# main.net
KiCad netlist of a schematic drawn in Altium Designer
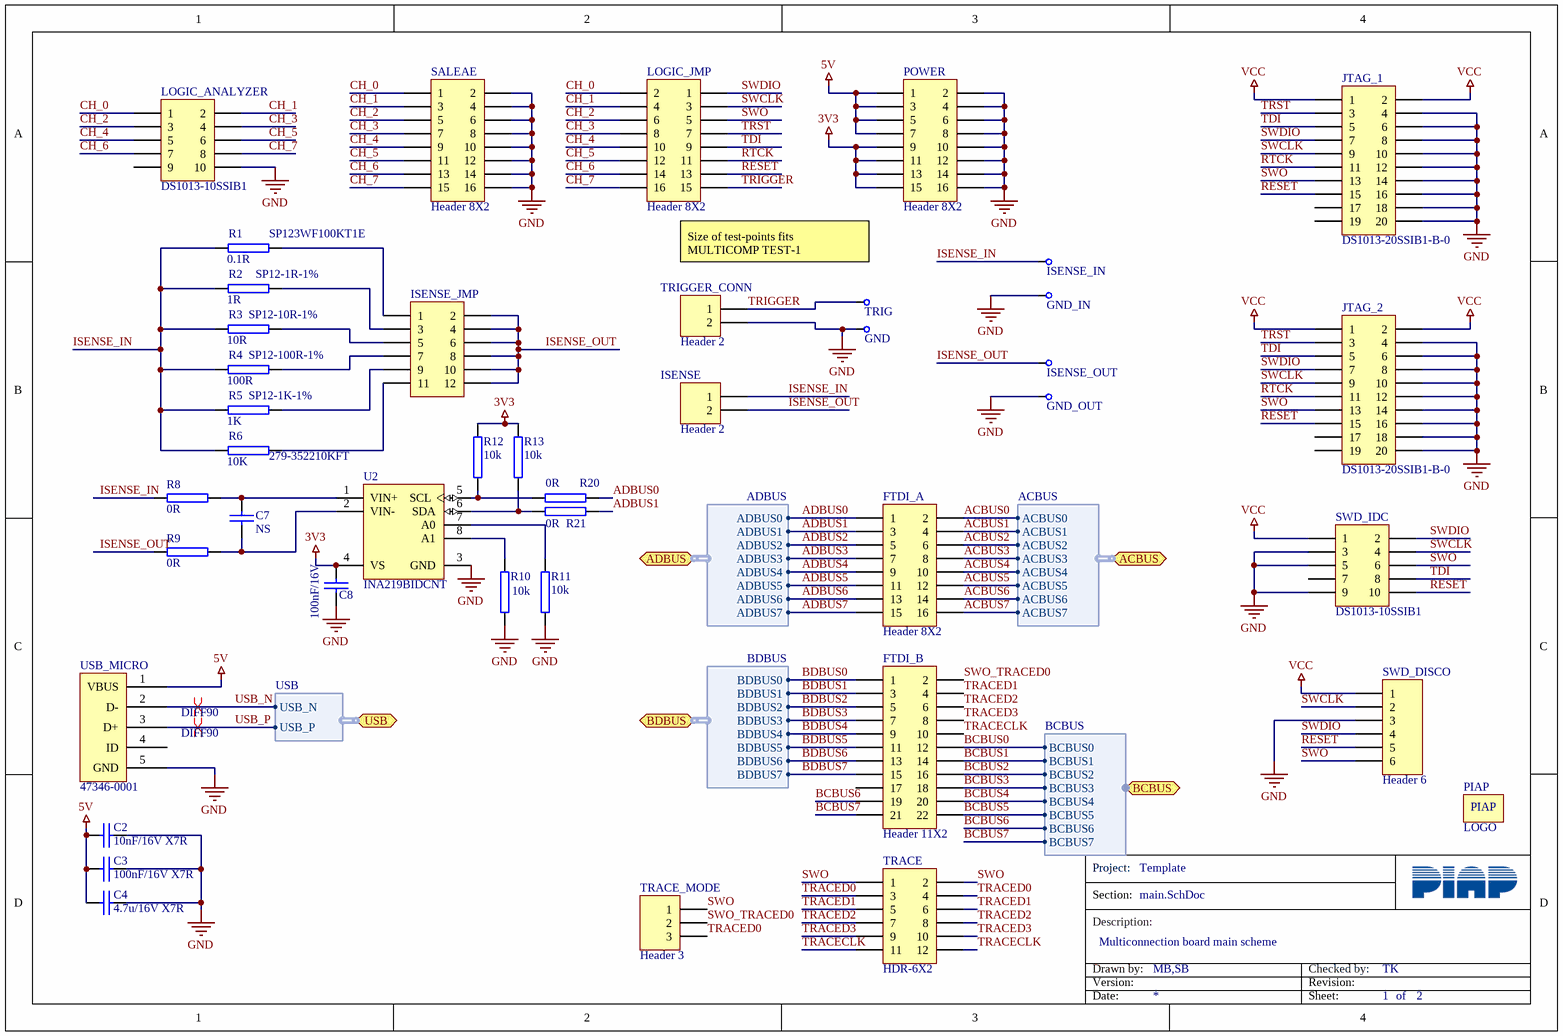
[diagram p0: main.SchDoc]

(export (version "E")
  (design (tool "Eeschema 10.0.6"))
  (components
    (comp (ref "C2")
      (value "10nF/16V X7R")
      (footprint "packages:0805")
      (description "Chip Capacitor 10nF/16V X7R")
      (fields (field (name "EMAIL") "AGrabowska@farnell.com"))
      (libsource (lib "capacitors") (part "n100"))
    )
    (comp (ref "C3")
      (value "100nF/16V X7R")
      (footprint "packages:0805")
      (description "Chip Capacitor 100nF/16V X7R")
      (fields (field (name "EMAIL") "AGrabowska@farnell.com"))
      (libsource (lib "capacitors") (part "n100"))
    )
    (comp (ref "C4")
      (value "4.7u/16V X7R")
      (footprint "packages:0805")
      (description "Chip Capacitor 4.7u/16V X7R")
      (fields (field (name "EMAIL") "AGrabowska@farnell.com"))
      (libsource (lib "capacitors") (part "n100"))
    )
    (comp (ref "C7")
      (value "NS")
      (footprint "packages:0603")
      (fields (field (name "EMAIL") "AGrabowska@farnell.com"))
      (libsource (lib "capacitors") (part "n100"))
    )
    (comp (ref "C8")
      (value "100nF/16V")
      (footprint "packages:0402")
      (description "NS")
      (fields (field (name "EMAIL") "AGrabowska@farnell.com"))
      (libsource (lib "capacitors") (part "n100"))
    )
    (comp (ref "FTDI_A")
      (value "Header 8X2")
      (footprint "connectors:HDR2X8")
      (description "Header, 16-Pin, Dual row, 2.54mm")
      (libsource (lib "") (part "Header 8X2_1"))
    )
    (comp (ref "FTDI_B")
      (value "Header 11X2")
      (footprint "connectors:HDR2X11")
      (description "Header, 22-Pin, Dual row, 2.54mm")
      (libsource (lib "connectors") (part "Header 11X2"))
    )
    (comp (ref "GND")
      (value "TEST_POINT_THT")
      (footprint "TEST_POINT_THT")
      (libsource (lib "no_bom") (part "TEST_POINT_THT"))
    )
    (comp (ref "GND_IN")
      (value "TEST_POINT_THT")
      (footprint "TEST_POINT_THT")
      (libsource (lib "no_bom") (part "TEST_POINT_THT"))
    )
    (comp (ref "GND_OUT")
      (value "TEST_POINT_THT")
      (footprint "TEST_POINT_THT")
      (libsource (lib "no_bom") (part "TEST_POINT_THT"))
    )
    (comp (ref "ISENSE")
      (value "Header 2")
      (footprint "HDR1X2")
      (description "Header, 2-Pin,  2.54mm")
      (libsource (lib "connectors") (part "Header 2"))
    )
    (comp (ref "ISENSE_IN")
      (value "TEST_POINT_THT")
      (footprint "TEST_POINT_THT")
      (libsource (lib "no_bom") (part "TEST_POINT_THT"))
    )
    (comp (ref "ISENSE_JMP")
      (value "~")
      (footprint "HDR2X6")
      (description "Header, 6-Pin, Dual row")
      (fields (field (name "PUBLISHER") "Altium Limited"))
      (libsource (lib "Miscellaneous Connectors") (part "Header 6X2"))
    )
    (comp (ref "ISENSE_OUT")
      (value "TEST_POINT_THT")
      (footprint "TEST_POINT_THT")
      (libsource (lib "no_bom") (part "TEST_POINT_THT"))
    )
    (comp (ref "JTAG_1")
      (value "DS1013-20SSIB1-B-0")
      (footprint "HDR2X10")
      (description "Header, 20-Pin, Dual row, 2.54mm")
      (libsource (lib "connectors") (part "Header 10X2"))
    )
    (comp (ref "JTAG_2")
      (value "DS1013-20SSIB1-B-0")
      (footprint "HDR2X10")
      (description "Header, 20-Pin, Dual row, 2.54mm")
      (libsource (lib "connectors") (part "Header 10X2"))
    )
    (comp (ref "LOGIC_ANALYZER")
      (value "DS1013-10SSIB1")
      (footprint "HDR2X5 socet")
      (description "Header, 10-Pin, Dual row, 2.54mm")
      (libsource (lib "connectors") (part "Header 5X2"))
    )
    (comp (ref "LOGIC_JMP")
      (value "Header 8X2")
      (footprint "HDR2X8")
      (description "Header, 16-Pin, Dual row, 2.54mm")
      (libsource (lib "connectors") (part "Header 8X2"))
    )
    (comp (ref "PIAP")
      (value "LOGO")
      (footprint "PIAP_5mm")
      (description "Logo PIAP")
      (libsource (lib "no_bom") (part "LOGO"))
    )
    (comp (ref "POWER")
      (value "Header 8X2")
      (footprint "HDR2X8")
      (description "Header, 16-Pin, Dual row, 2.54mm")
      (libsource (lib "") (part "Header 8X2_1"))
    )
    (comp (ref "R1")
      (value "0.1R")
      (footprint "packages:2512")
      (description "Resistor 0.1R 3W 1%")
      (fields
        (field (name "MANUFACTURER") "Royal Electronic Factory")
        (field (name "MANUFACTURER PART NUMBER") "SP123WF100KT1E")
      )
      (libsource (lib "resistors") (part "1R"))
    )
    (comp (ref "R2")
      (value "1R")
      (footprint "packages:2512")
      (description "Resistor 1R 3W 1%")
      (fields
        (field (name "SUPPLIER PART NUMBER 1") "SP12-1R-1%")
        (field (name "MANUFACTURER") "Royal Electronic Factory")
        (field (name "MANUFACTURER PART NUMBER") "SP123WF100KT1E")
      )
      (libsource (lib "resistors") (part "1R"))
    )
    (comp (ref "R3")
      (value "10R")
      (footprint "packages:2512")
      (description "Resistor 10R 3W 1%")
      (fields
        (field (name "SUPPLIER PART NUMBER 1") "SP12-10R-1%")
        (field (name "MANUFACTURER") "Royal Electronic Factory")
        (field (name "MANUFACTURER PART NUMBER") "SP123WF100JT1E")
      )
      (libsource (lib "resistors") (part "1R"))
    )
    (comp (ref "R4")
      (value "100R")
      (footprint "packages:2512")
      (description "Resistor 100R 2W 1%")
      (fields
        (field (name "SUPPLIER PART NUMBER 1") "SP12-100R-1%")
        (field (name "MANUFACTURER") "Royal Electronic Factory")
        (field (name "MANUFACTURER PART NUMBER") "SP123WJ0101T1E")
      )
      (libsource (lib "resistors") (part "1R"))
    )
    (comp (ref "R5")
      (value "1K")
      (footprint "packages:2512")
      (description "Resistor 1k 2W 1%")
      (fields
        (field (name "SUPPLIER PART NUMBER 1") "SP12-1K-1%")
        (field (name "MANUFACTURER") "Royal Electronic Factory")
        (field (name "MANUFACTURER PART NUMBER") "SP123WF1001T1E")
      )
      (libsource (lib "resistors") (part "1R"))
    )
    (comp (ref "R6")
      (value "10K")
      (footprint "packages:2512")
      (description "Resistor 10K 3W 1%")
      (fields
        (field (name "MANUFACTURER") "Royal Electronic Factory")
        (field (name "MANUFACTURER PART NUMBER") "SP123WF100KT1E")
        (field (name "SUPPLIER PART NUMBER 3") "279-352210KFT")
      )
      (libsource (lib "resistors") (part "1R"))
    )
    (comp (ref "R8")
      (value "0R")
      (footprint "packages:0603")
      (description "Chip Resistor 0Ohm 0.25W")
      (libsource (lib "resistors") (part "k100"))
    )
    (comp (ref "R9")
      (value "0R")
      (footprint "packages:0603")
      (description "Chip Resistor 0 Ohm 0.25W")
      (libsource (lib "resistors") (part "k100"))
    )
    (comp (ref "R10")
      (value "10k")
      (footprint "packages:0603")
      (description "Chip Resistor 0Ohm 0.25W")
      (libsource (lib "resistors") (part "k100"))
    )
    (comp (ref "R11")
      (value "10k")
      (footprint "packages:0603")
      (description "Chip Resistor 0Ohm 0.25W")
      (libsource (lib "resistors") (part "k100"))
    )
    (comp (ref "R12")
      (value "10k")
      (footprint "packages:0603")
      (description "Chip Resistor 0Ohm 0.25W")
      (libsource (lib "resistors") (part "k100"))
    )
    (comp (ref "R13")
      (value "10k")
      (footprint "packages:0603")
      (description "Chip Resistor 0Ohm 0.25W")
      (libsource (lib "resistors") (part "k100"))
    )
    (comp (ref "R20")
      (value "0R")
      (footprint "packages:0603")
      (description "Chip Resistor 0Ohm 0.25W")
      (libsource (lib "resistors") (part "k100"))
    )
    (comp (ref "R21")
      (value "0R")
      (footprint "packages:0603")
      (description "Chip Resistor 0Ohm 0.25W")
      (libsource (lib "resistors") (part "k100"))
    )
    (comp (ref "SALEAE")
      (value "Header 8X2")
      (footprint "HDR2X8")
      (description "Header, 16-Pin, Dual row, 2.54mm")
      (libsource (lib "") (part "Header 8X2_1"))
    )
    (comp (ref "SWD_DISCO")
      (value "Header 6")
      (footprint "connectors:HDR1X6")
      (description "Header, 6-Pin, 2.54mm")
      (libsource (lib "connectors") (part "Header 6"))
    )
    (comp (ref "SWD_IDC")
      (value "DS1013-10SSIB1")
      (footprint "HDR2X5 socet")
      (description "Header, 10-Pin, Dual row, 2.54mm")
      (libsource (lib "connectors") (part "Header 5X2"))
    )
    (comp (ref "TRACE")
      (value "HDR-6X2")
      (footprint "connectors:HDR2X6")
      (description "Header, 12-Pin, Dual row, SMD, 2.54mm")
      (libsource (lib "connectors") (part "Header 6X2"))
    )
    (comp (ref "TRACE_MODE")
      (value "Header 3")
      (footprint "connectors:HDR1X3")
      (description "Header, 3-Pin,  2.54mm")
      (libsource (lib "connectors") (part "Header 3"))
    )
    (comp (ref "TRIG")
      (value "TEST_POINT_THT")
      (footprint "TEST_POINT_THT")
      (libsource (lib "no_bom") (part "TEST_POINT_THT"))
    )
    (comp (ref "TRIGGER_CONN")
      (value "Header 2")
      (footprint "HDR1X2")
      (description "Header, 2-Pin,  2.54mm")
      (libsource (lib "connectors") (part "Header 2"))
    )
    (comp (ref "U2")
      (value "INA219BIDCNT")
      (footprint "DCN0008A_M")
      (fields (field (name "MANUFACTURER") "Texas Instruments"))
      (libsource (lib "Altium Content Vault") (part "TI-INA219DCN8"))
    )
    (comp (ref "USB_MICRO")
      (value "47346-0001")
      (footprint "47346-0001")
      (libsource (lib "connectors") (part "47346-0001"))
    )
  )
  (nets
    (net (code "6") (name "/ACBUS0") (class "Default")
      (node (ref "FTDI_A") (pin "2") (pinfunction "2_2") (pintype "passive"))
    )
    (net (code "7") (name "/ACBUS1") (class "Default")
      (node (ref "FTDI_A") (pin "4") (pinfunction "4_4") (pintype "passive"))
    )
    (net (code "8") (name "/ACBUS2") (class "Default")
      (node (ref "FTDI_A") (pin "6") (pinfunction "6_6") (pintype "passive"))
    )
    (net (code "9") (name "/ACBUS3") (class "Default")
      (node (ref "FTDI_A") (pin "8") (pinfunction "8_8") (pintype "passive"))
    )
    (net (code "10") (name "/ACBUS4") (class "Default")
      (node (ref "FTDI_A") (pin "10") (pinfunction "10_10") (pintype "passive"))
    )
    (net (code "11") (name "/ACBUS5") (class "Default")
      (node (ref "FTDI_A") (pin "12") (pinfunction "12_12") (pintype "passive"))
    )
    (net (code "12") (name "/ACBUS6") (class "Default")
      (node (ref "FTDI_A") (pin "14") (pinfunction "14_14") (pintype "passive"))
    )
    (net (code "13") (name "/ACBUS7") (class "Default")
      (node (ref "FTDI_A") (pin "16") (pinfunction "16_16") (pintype "passive"))
    )
    (net (code "14") (name "/ADBUS0") (class "Default")
      (node (ref "FTDI_A") (pin "1") (pinfunction "1_1") (pintype "passive"))
      (node (ref "R20") (pin "1") (pinfunction "1_1") (pintype "passive"))
    )
    (net (code "15") (name "/ADBUS1") (class "Default")
      (node (ref "FTDI_A") (pin "3") (pinfunction "3_3") (pintype "passive"))
      (node (ref "R21") (pin "1") (pinfunction "1_1") (pintype "passive"))
    )
    (net (code "16") (name "/ADBUS2") (class "Default")
      (node (ref "FTDI_A") (pin "5") (pinfunction "5_5") (pintype "passive"))
    )
    (net (code "17") (name "/ADBUS3") (class "Default")
      (node (ref "FTDI_A") (pin "7") (pinfunction "7_7") (pintype "passive"))
    )
    (net (code "18") (name "/ADBUS4") (class "Default")
      (node (ref "FTDI_A") (pin "9") (pinfunction "9_9") (pintype "passive"))
    )
    (net (code "19") (name "/ADBUS5") (class "Default")
      (node (ref "FTDI_A") (pin "11") (pinfunction "11_11") (pintype "passive"))
    )
    (net (code "20") (name "/ADBUS6") (class "Default")
      (node (ref "FTDI_A") (pin "13") (pinfunction "13_13") (pintype "passive"))
    )
    (net (code "21") (name "/ADBUS7") (class "Default")
      (node (ref "FTDI_A") (pin "15") (pinfunction "15_15") (pintype "passive"))
    )
    (net (code "22") (name "/BCBUS0") (class "Default")
      (node (ref "FTDI_B") (pin "12") (pinfunction "12_12") (pintype "passive"))
    )
    (net (code "23") (name "/BCBUS1") (class "Default")
      (node (ref "FTDI_B") (pin "14") (pinfunction "14_14") (pintype "passive"))
    )
    (net (code "24") (name "/BCBUS2") (class "Default")
      (node (ref "FTDI_B") (pin "16") (pinfunction "16_16") (pintype "passive"))
    )
    (net (code "25") (name "/BCBUS3") (class "Default")
      (node (ref "FTDI_B") (pin "18") (pinfunction "18_18") (pintype "passive"))
    )
    (net (code "26") (name "/BCBUS4") (class "Default")
      (node (ref "FTDI_B") (pin "20") (pinfunction "20_20") (pintype "passive"))
    )
    (net (code "27") (name "/BCBUS5") (class "Default")
      (node (ref "FTDI_B") (pin "22") (pinfunction "22_22") (pintype "passive"))
    )
    (net (code "28") (name "/BCBUS6") (class "Default")
      (node (ref "FTDI_B") (pin "19") (pinfunction "19_19") (pintype "passive"))
    )
    (net (code "29") (name "/BCBUS7") (class "Default")
      (node (ref "FTDI_B") (pin "21") (pinfunction "21_21") (pintype "passive"))
    )
    (net (code "30") (name "/BDBUS0") (class "Default")
      (node (ref "FTDI_B") (pin "1") (pinfunction "1_1") (pintype "passive"))
    )
    (net (code "31") (name "/BDBUS1") (class "Default")
      (node (ref "FTDI_B") (pin "3") (pinfunction "3_3") (pintype "passive"))
    )
    (net (code "32") (name "/BDBUS2") (class "Default")
      (node (ref "FTDI_B") (pin "5") (pinfunction "5_5") (pintype "passive"))
    )
    (net (code "33") (name "/BDBUS3") (class "Default")
      (node (ref "FTDI_B") (pin "7") (pinfunction "7_7") (pintype "passive"))
    )
    (net (code "34") (name "/BDBUS4") (class "Default")
      (node (ref "FTDI_B") (pin "9") (pinfunction "9_9") (pintype "passive"))
    )
    (net (code "35") (name "/BDBUS5") (class "Default")
      (node (ref "FTDI_B") (pin "11") (pinfunction "11_11") (pintype "passive"))
    )
    (net (code "36") (name "/BDBUS6") (class "Default")
      (node (ref "FTDI_B") (pin "13") (pinfunction "13_13") (pintype "passive"))
    )
    (net (code "37") (name "/BDBUS7") (class "Default")
      (node (ref "FTDI_B") (pin "15") (pinfunction "15_15") (pintype "passive"))
    )
    (net (code "38") (name "/CH_0") (class "Default")
      (node (ref "LOGIC_ANALYZER") (pin "1") (pinfunction "1_1") (pintype "passive"))
      (node (ref "LOGIC_JMP") (pin "2") (pinfunction "2_2") (pintype "passive"))
      (node (ref "SALEAE") (pin "1") (pinfunction "1_1") (pintype "passive"))
    )
    (net (code "39") (name "/CH_1") (class "Default")
      (node (ref "LOGIC_ANALYZER") (pin "2") (pinfunction "2_2") (pintype "passive"))
      (node (ref "LOGIC_JMP") (pin "4") (pinfunction "4_4") (pintype "passive"))
      (node (ref "SALEAE") (pin "3") (pinfunction "3_3") (pintype "passive"))
    )
    (net (code "40") (name "/CH_2") (class "Default")
      (node (ref "LOGIC_ANALYZER") (pin "3") (pinfunction "3_3") (pintype "passive"))
      (node (ref "LOGIC_JMP") (pin "6") (pinfunction "6_6") (pintype "passive"))
      (node (ref "SALEAE") (pin "5") (pinfunction "5_5") (pintype "passive"))
    )
    (net (code "41") (name "/CH_3") (class "Default")
      (node (ref "LOGIC_ANALYZER") (pin "4") (pinfunction "4_4") (pintype "passive"))
      (node (ref "LOGIC_JMP") (pin "8") (pinfunction "8_8") (pintype "passive"))
      (node (ref "SALEAE") (pin "7") (pinfunction "7_7") (pintype "passive"))
    )
    (net (code "42") (name "/CH_4") (class "Default")
      (node (ref "LOGIC_ANALYZER") (pin "5") (pinfunction "5_5") (pintype "passive"))
      (node (ref "LOGIC_JMP") (pin "10") (pinfunction "10_10") (pintype "passive"))
      (node (ref "SALEAE") (pin "9") (pinfunction "9_9") (pintype "passive"))
    )
    (net (code "43") (name "/CH_5") (class "Default")
      (node (ref "LOGIC_ANALYZER") (pin "6") (pinfunction "6_6") (pintype "passive"))
      (node (ref "LOGIC_JMP") (pin "12") (pinfunction "12_12") (pintype "passive"))
      (node (ref "SALEAE") (pin "11") (pinfunction "11_11") (pintype "passive"))
    )
    (net (code "44") (name "/CH_6") (class "Default")
      (node (ref "LOGIC_ANALYZER") (pin "7") (pinfunction "7_7") (pintype "passive"))
      (node (ref "LOGIC_JMP") (pin "14") (pinfunction "14_14") (pintype "passive"))
      (node (ref "SALEAE") (pin "13") (pinfunction "13_13") (pintype "passive"))
    )
    (net (code "45") (name "/CH_7") (class "Default")
      (node (ref "LOGIC_ANALYZER") (pin "8") (pinfunction "8_8") (pintype "passive"))
      (node (ref "LOGIC_JMP") (pin "16") (pinfunction "16_16") (pintype "passive"))
      (node (ref "SALEAE") (pin "15") (pinfunction "15_15") (pintype "passive"))
    )
    (net (code "46") (name "/ISENSE_IN") (class "Default")
      (node (ref "ISENSE") (pin "1") (pinfunction "1_1") (pintype "passive"))
      (node (ref "ISENSE_IN") (pin "1") (pinfunction "1_1") (pintype "passive"))
      (node (ref "R1") (pin "1") (pinfunction "1_1") (pintype "passive"))
      (node (ref "R2") (pin "1") (pinfunction "1_1") (pintype "passive"))
      (node (ref "R3") (pin "1") (pinfunction "1_1") (pintype "passive"))
      (node (ref "R4") (pin "1") (pinfunction "1_1") (pintype "passive"))
      (node (ref "R5") (pin "1") (pinfunction "1_1") (pintype "passive"))
      (node (ref "R6") (pin "1") (pinfunction "1_1") (pintype "passive"))
      (node (ref "R8") (pin "2") (pinfunction "2_2") (pintype "passive"))
    )
    (net (code "47") (name "/ISENSE_OUT") (class "Default")
      (node (ref "ISENSE") (pin "2") (pinfunction "2_2") (pintype "passive"))
      (node (ref "ISENSE_JMP") (pin "10") (pinfunction "10_10") (pintype "passive"))
      (node (ref "ISENSE_JMP") (pin "12") (pinfunction "12_12") (pintype "passive"))
      (node (ref "ISENSE_JMP") (pin "2") (pinfunction "2_2") (pintype "passive"))
      (node (ref "ISENSE_JMP") (pin "4") (pinfunction "4_4") (pintype "passive"))
      (node (ref "ISENSE_JMP") (pin "6") (pinfunction "6_6") (pintype "passive"))
      (node (ref "ISENSE_JMP") (pin "8") (pinfunction "8_8") (pintype "passive"))
      (node (ref "ISENSE_OUT") (pin "1") (pinfunction "1_1") (pintype "passive"))
      (node (ref "R9") (pin "2") (pinfunction "2_2") (pintype "passive"))
    )
    (net (code "48") (name "/RESET") (class "Default")
      (node (ref "JTAG_1") (pin "15") (pinfunction "15_15") (pintype "passive"))
      (node (ref "JTAG_2") (pin "15") (pinfunction "15_15") (pintype "passive"))
      (node (ref "LOGIC_JMP") (pin "13") (pinfunction "13_13") (pintype "passive"))
      (node (ref "SWD_DISCO") (pin "5") (pinfunction "5_5") (pintype "passive"))
      (node (ref "SWD_IDC") (pin "10") (pinfunction "10_10") (pintype "passive"))
    )
    (net (code "49") (name "/RTCK") (class "Default")
      (node (ref "JTAG_1") (pin "11") (pinfunction "11_11") (pintype "passive"))
      (node (ref "JTAG_2") (pin "11") (pinfunction "11_11") (pintype "passive"))
      (node (ref "LOGIC_JMP") (pin "11") (pinfunction "11_11") (pintype "passive"))
    )
    (net (code "50") (name "/SWCLK") (class "Default")
      (node (ref "JTAG_1") (pin "9") (pinfunction "9_9") (pintype "passive"))
      (node (ref "JTAG_2") (pin "9") (pinfunction "9_9") (pintype "passive"))
      (node (ref "LOGIC_JMP") (pin "3") (pinfunction "3_3") (pintype "passive"))
      (node (ref "SWD_DISCO") (pin "2") (pinfunction "2_2") (pintype "passive"))
      (node (ref "SWD_IDC") (pin "4") (pinfunction "4_4") (pintype "passive"))
    )
    (net (code "51") (name "/SWDIO") (class "Default")
      (node (ref "JTAG_1") (pin "7") (pinfunction "7_7") (pintype "passive"))
      (node (ref "JTAG_2") (pin "7") (pinfunction "7_7") (pintype "passive"))
      (node (ref "LOGIC_JMP") (pin "1") (pinfunction "1_1") (pintype "passive"))
      (node (ref "SWD_DISCO") (pin "4") (pinfunction "4_4") (pintype "passive"))
      (node (ref "SWD_IDC") (pin "2") (pinfunction "2_2") (pintype "passive"))
    )
    (net (code "52") (name "/SWO") (class "Default")
      (node (ref "JTAG_1") (pin "13") (pinfunction "13_13") (pintype "passive"))
      (node (ref "JTAG_2") (pin "13") (pinfunction "13_13") (pintype "passive"))
      (node (ref "LOGIC_JMP") (pin "5") (pinfunction "5_5") (pintype "passive"))
      (node (ref "SWD_DISCO") (pin "6") (pinfunction "6_6") (pintype "passive"))
      (node (ref "SWD_IDC") (pin "6") (pinfunction "6_6") (pintype "passive"))
      (node (ref "TRACE") (pin "1") (pinfunction "1_1") (pintype "passive"))
      (node (ref "TRACE") (pin "2") (pinfunction "2_2") (pintype "passive"))
      (node (ref "TRACE_MODE") (pin "1") (pinfunction "1_1") (pintype "passive"))
    )
    (net (code "53") (name "/SWO_TRACED0") (class "Default")
      (node (ref "FTDI_B") (pin "2") (pinfunction "2_2") (pintype "passive"))
      (node (ref "TRACE_MODE") (pin "2") (pinfunction "2_2") (pintype "passive"))
    )
    (net (code "54") (name "/TDI") (class "Default")
      (node (ref "JTAG_1") (pin "5") (pinfunction "5_5") (pintype "passive"))
      (node (ref "JTAG_2") (pin "5") (pinfunction "5_5") (pintype "passive"))
      (node (ref "LOGIC_JMP") (pin "9") (pinfunction "9_9") (pintype "passive"))
      (node (ref "SWD_IDC") (pin "8") (pinfunction "8_8") (pintype "passive"))
    )
    (net (code "55") (name "/TRACECLK") (class "Default")
      (node (ref "FTDI_B") (pin "10") (pinfunction "10_10") (pintype "passive"))
      (node (ref "TRACE") (pin "11") (pinfunction "11_11") (pintype "passive"))
      (node (ref "TRACE") (pin "12") (pinfunction "12_12") (pintype "passive"))
    )
    (net (code "56") (name "/TRACED0") (class "Default")
      (node (ref "TRACE") (pin "3") (pinfunction "3_3") (pintype "passive"))
      (node (ref "TRACE") (pin "4") (pinfunction "4_4") (pintype "passive"))
      (node (ref "TRACE_MODE") (pin "3") (pinfunction "3_3") (pintype "passive"))
    )
    (net (code "57") (name "/TRACED1") (class "Default")
      (node (ref "FTDI_B") (pin "4") (pinfunction "4_4") (pintype "passive"))
      (node (ref "TRACE") (pin "5") (pinfunction "5_5") (pintype "passive"))
      (node (ref "TRACE") (pin "6") (pinfunction "6_6") (pintype "passive"))
    )
    (net (code "58") (name "/TRACED2") (class "Default")
      (node (ref "FTDI_B") (pin "6") (pinfunction "6_6") (pintype "passive"))
      (node (ref "TRACE") (pin "7") (pinfunction "7_7") (pintype "passive"))
      (node (ref "TRACE") (pin "8") (pinfunction "8_8") (pintype "passive"))
    )
    (net (code "59") (name "/TRACED3") (class "Default")
      (node (ref "FTDI_B") (pin "8") (pinfunction "8_8") (pintype "passive"))
      (node (ref "TRACE") (pin "10") (pinfunction "10_10") (pintype "passive"))
      (node (ref "TRACE") (pin "9") (pinfunction "9_9") (pintype "passive"))
    )
    (net (code "60") (name "/TRIGGER") (class "Default")
      (node (ref "LOGIC_JMP") (pin "15") (pinfunction "15_15") (pintype "passive"))
      (node (ref "TRIG") (pin "1") (pinfunction "1_1") (pintype "passive"))
      (node (ref "TRIGGER_CONN") (pin "1") (pinfunction "1_1") (pintype "passive"))
    )
    (net (code "61") (name "/TRST") (class "Default")
      (node (ref "JTAG_1") (pin "3") (pinfunction "3_3") (pintype "passive"))
      (node (ref "JTAG_2") (pin "3") (pinfunction "3_3") (pintype "passive"))
      (node (ref "LOGIC_JMP") (pin "7") (pinfunction "7_7") (pintype "passive"))
    )
    (net (code "62") (name "/USB_N") (class "Default")
      (node (ref "USB_MICRO") (pin "2") (pinfunction "D-_2") (pintype "passive"))
    )
    (net (code "63") (name "/USB_P") (class "Default")
      (node (ref "USB_MICRO") (pin "3") (pinfunction "D+_3") (pintype "passive"))
    )
    (net (code "69") (name "3V3") (class "Default")
      (node (ref "C8") (pin "1") (pinfunction "1_1") (pintype "passive"))
      (node (ref "POWER") (pin "11") (pinfunction "11_11") (pintype "passive"))
      (node (ref "POWER") (pin "13") (pinfunction "13_13") (pintype "passive"))
      (node (ref "POWER") (pin "15") (pinfunction "15_15") (pintype "passive"))
      (node (ref "POWER") (pin "9") (pinfunction "9_9") (pintype "passive"))
      (node (ref "R12") (pin "2") (pinfunction "2_2") (pintype "passive"))
      (node (ref "R13") (pin "2") (pinfunction "2_2") (pintype "passive"))
      (node (ref "U2") (pin "4") (pinfunction "VS_4") (pintype "power_in"))
    )
    (net (code "70") (name "5V") (class "Default")
      (node (ref "C2") (pin "2") (pinfunction "2_2") (pintype "passive"))
      (node (ref "C3") (pin "1") (pinfunction "1_1") (pintype "passive"))
      (node (ref "C4") (pin "2") (pinfunction "2_2") (pintype "passive"))
      (node (ref "POWER") (pin "1") (pinfunction "1_1") (pintype "passive"))
      (node (ref "POWER") (pin "3") (pinfunction "3_3") (pintype "passive"))
      (node (ref "POWER") (pin "5") (pinfunction "5_5") (pintype "passive"))
      (node (ref "POWER") (pin "7") (pinfunction "7_7") (pintype "passive"))
      (node (ref "USB_MICRO") (pin "1") (pinfunction "VBUS_1") (pintype "passive"))
    )
    (net (code "71") (name "GND") (class "Default")
      (node (ref "C2") (pin "1") (pinfunction "1_1") (pintype "passive"))
      (node (ref "C3") (pin "2") (pinfunction "2_2") (pintype "passive"))
      (node (ref "C4") (pin "1") (pinfunction "1_1") (pintype "passive"))
      (node (ref "C8") (pin "2") (pinfunction "2_2") (pintype "passive"))
      (node (ref "GND") (pin "1") (pinfunction "1_1") (pintype "passive"))
      (node (ref "GND_IN") (pin "1") (pinfunction "1_1") (pintype "passive"))
      (node (ref "GND_OUT") (pin "1") (pinfunction "1_1") (pintype "passive"))
      (node (ref "JTAG_1") (pin "10") (pinfunction "10_10") (pintype "passive"))
      (node (ref "JTAG_1") (pin "12") (pinfunction "12_12") (pintype "passive"))
      (node (ref "JTAG_1") (pin "14") (pinfunction "14_14") (pintype "passive"))
      (node (ref "JTAG_1") (pin "16") (pinfunction "16_16") (pintype "passive"))
      (node (ref "JTAG_1") (pin "18") (pinfunction "18_18") (pintype "passive"))
      (node (ref "JTAG_1") (pin "20") (pinfunction "20_20") (pintype "passive"))
      (node (ref "JTAG_1") (pin "4") (pinfunction "4_4") (pintype "passive"))
      (node (ref "JTAG_1") (pin "6") (pinfunction "6_6") (pintype "passive"))
      (node (ref "JTAG_1") (pin "8") (pinfunction "8_8") (pintype "passive"))
      (node (ref "JTAG_2") (pin "10") (pinfunction "10_10") (pintype "passive"))
      (node (ref "JTAG_2") (pin "12") (pinfunction "12_12") (pintype "passive"))
      (node (ref "JTAG_2") (pin "14") (pinfunction "14_14") (pintype "passive"))
      (node (ref "JTAG_2") (pin "16") (pinfunction "16_16") (pintype "passive"))
      (node (ref "JTAG_2") (pin "18") (pinfunction "18_18") (pintype "passive"))
      (node (ref "JTAG_2") (pin "20") (pinfunction "20_20") (pintype "passive"))
      (node (ref "JTAG_2") (pin "4") (pinfunction "4_4") (pintype "passive"))
      (node (ref "JTAG_2") (pin "6") (pinfunction "6_6") (pintype "passive"))
      (node (ref "JTAG_2") (pin "8") (pinfunction "8_8") (pintype "passive"))
      (node (ref "LOGIC_ANALYZER") (pin "10") (pinfunction "10_10") (pintype "passive"))
      (node (ref "POWER") (pin "10") (pinfunction "10_10") (pintype "passive"))
      (node (ref "POWER") (pin "12") (pinfunction "12_12") (pintype "passive"))
      (node (ref "POWER") (pin "14") (pinfunction "14_14") (pintype "passive"))
      (node (ref "POWER") (pin "16") (pinfunction "16_16") (pintype "passive"))
      (node (ref "POWER") (pin "2") (pinfunction "2_2") (pintype "passive"))
      (node (ref "POWER") (pin "4") (pinfunction "4_4") (pintype "passive"))
      (node (ref "POWER") (pin "6") (pinfunction "6_6") (pintype "passive"))
      (node (ref "POWER") (pin "8") (pinfunction "8_8") (pintype "passive"))
      (node (ref "R10") (pin "2") (pinfunction "2_2") (pintype "passive"))
      (node (ref "R11") (pin "2") (pinfunction "2_2") (pintype "passive"))
      (node (ref "SALEAE") (pin "10") (pinfunction "10_10") (pintype "passive"))
      (node (ref "SALEAE") (pin "12") (pinfunction "12_12") (pintype "passive"))
      (node (ref "SALEAE") (pin "14") (pinfunction "14_14") (pintype "passive"))
      (node (ref "SALEAE") (pin "16") (pinfunction "16_16") (pintype "passive"))
      (node (ref "SALEAE") (pin "2") (pinfunction "2_2") (pintype "passive"))
      (node (ref "SALEAE") (pin "4") (pinfunction "4_4") (pintype "passive"))
      (node (ref "SALEAE") (pin "6") (pinfunction "6_6") (pintype "passive"))
      (node (ref "SALEAE") (pin "8") (pinfunction "8_8") (pintype "passive"))
      (node (ref "SWD_DISCO") (pin "3") (pinfunction "3_3") (pintype "passive"))
      (node (ref "SWD_IDC") (pin "3") (pinfunction "3_3") (pintype "passive"))
      (node (ref "SWD_IDC") (pin "5") (pinfunction "5_5") (pintype "passive"))
      (node (ref "SWD_IDC") (pin "9") (pinfunction "9_9") (pintype "passive"))
      (node (ref "TRIGGER_CONN") (pin "2") (pinfunction "2_2") (pintype "passive"))
      (node (ref "U2") (pin "3") (pinfunction "GND_3") (pintype "power_in"))
      (node (ref "USB_MICRO") (pin "5") (pinfunction "GND_5") (pintype "passive"))
    )
    (net (code "72") (name "Net-(ISENSE_JMP-Pad1)") (class "Default")
      (node (ref "ISENSE_JMP") (pin "1") (pinfunction "1_1") (pintype "passive"))
      (node (ref "R1") (pin "2") (pinfunction "2_2") (pintype "passive"))
    )
    (net (code "73") (name "Net-(ISENSE_JMP-Pad3)") (class "Default")
      (node (ref "ISENSE_JMP") (pin "3") (pinfunction "3_3") (pintype "passive"))
      (node (ref "R2") (pin "2") (pinfunction "2_2") (pintype "passive"))
    )
    (net (code "74") (name "Net-(ISENSE_JMP-Pad5)") (class "Default")
      (node (ref "ISENSE_JMP") (pin "5") (pinfunction "5_5") (pintype "passive"))
      (node (ref "R3") (pin "2") (pinfunction "2_2") (pintype "passive"))
    )
    (net (code "75") (name "Net-(ISENSE_JMP-Pad7)") (class "Default")
      (node (ref "ISENSE_JMP") (pin "7") (pinfunction "7_7") (pintype "passive"))
      (node (ref "R4") (pin "2") (pinfunction "2_2") (pintype "passive"))
    )
    (net (code "76") (name "Net-(ISENSE_JMP-Pad9)") (class "Default")
      (node (ref "ISENSE_JMP") (pin "9") (pinfunction "9_9") (pintype "passive"))
      (node (ref "R5") (pin "2") (pinfunction "2_2") (pintype "passive"))
    )
    (net (code "77") (name "Net-(ISENSE_JMP-Pad11)") (class "Default")
      (node (ref "ISENSE_JMP") (pin "11") (pinfunction "11_11") (pintype "passive"))
      (node (ref "R6") (pin "2") (pinfunction "2_2") (pintype "passive"))
    )
    (net (code "78") (name "Net-(U2-A0)") (class "Default")
      (node (ref "R11") (pin "1") (pinfunction "1_1") (pintype "passive"))
      (node (ref "U2") (pin "7") (pinfunction "A0_7") (pintype "open_collector"))
    )
    (net (code "79") (name "Net-(U2-A1)") (class "Default")
      (node (ref "R10") (pin "1") (pinfunction "1_1") (pintype "passive"))
      (node (ref "U2") (pin "8") (pinfunction "A1_8") (pintype "open_collector"))
    )
    (net (code "80") (name "Net-(U2-SCL)") (class "Default")
      (node (ref "R12") (pin "1") (pinfunction "1_1") (pintype "passive"))
      (node (ref "R20") (pin "2") (pinfunction "2_2") (pintype "passive"))
      (node (ref "U2") (pin "5") (pinfunction "SCL_5") (pintype "bidirectional"))
    )
    (net (code "81") (name "Net-(U2-SDA)") (class "Default")
      (node (ref "R13") (pin "1") (pinfunction "1_1") (pintype "passive"))
      (node (ref "R21") (pin "2") (pinfunction "2_2") (pintype "passive"))
      (node (ref "U2") (pin "6") (pinfunction "SDA_6") (pintype "bidirectional"))
    )
    (net (code "82") (name "Net-(U2-VIN+)") (class "Default")
      (node (ref "C7") (pin "2") (pinfunction "2_2") (pintype "passive"))
      (node (ref "R8") (pin "1") (pinfunction "1_1") (pintype "passive"))
      (node (ref "U2") (pin "1") (pinfunction "VIN+_1") (pintype "open_collector"))
    )
    (net (code "83") (name "Net-(U2-VIN-)") (class "Default")
      (node (ref "C7") (pin "1") (pinfunction "1_1") (pintype "passive"))
      (node (ref "R9") (pin "1") (pinfunction "1_1") (pintype "passive"))
      (node (ref "U2") (pin "2") (pinfunction "VIN-_2") (pintype "open_collector"))
    )
    (net (code "84") (name "VCC") (class "Default")
      (node (ref "JTAG_1") (pin "1") (pinfunction "1_1") (pintype "passive"))
      (node (ref "JTAG_1") (pin "2") (pinfunction "2_2") (pintype "passive"))
      (node (ref "JTAG_2") (pin "1") (pinfunction "1_1") (pintype "passive"))
      (node (ref "JTAG_2") (pin "2") (pinfunction "2_2") (pintype "passive"))
      (node (ref "SWD_DISCO") (pin "1") (pinfunction "1_1") (pintype "passive"))
      (node (ref "SWD_IDC") (pin "1") (pinfunction "1_1") (pintype "passive"))
    )
    (net (code "85") (name "unconnected-(FTDI_B-Pad17)") (class "Default")
      (node (ref "FTDI_B") (pin "17") (pinfunction "17_17") (pintype "passive"))
    )
    (net (code "86") (name "unconnected-(JTAG_1-Pad17)") (class "Default")
      (node (ref "JTAG_1") (pin "17") (pinfunction "17_17") (pintype "passive"))
    )
    (net (code "87") (name "unconnected-(JTAG_1-Pad19)") (class "Default")
      (node (ref "JTAG_1") (pin "19") (pinfunction "19_19") (pintype "passive"))
    )
    (net (code "88") (name "unconnected-(JTAG_2-Pad17)") (class "Default")
      (node (ref "JTAG_2") (pin "17") (pinfunction "17_17") (pintype "passive"))
    )
    (net (code "89") (name "unconnected-(JTAG_2-Pad19)") (class "Default")
      (node (ref "JTAG_2") (pin "19") (pinfunction "19_19") (pintype "passive"))
    )
    (net (code "90") (name "unconnected-(LOGIC_ANALYZER-Pad9)") (class "Default")
      (node (ref "LOGIC_ANALYZER") (pin "9") (pinfunction "9_9") (pintype "passive"))
    )
    (net (code "91") (name "unconnected-(SWD_IDC-Pad7)") (class "Default")
      (node (ref "SWD_IDC") (pin "7") (pinfunction "7_7") (pintype "passive"))
    )
    (net (code "92") (name "unconnected-(USB_MICRO-ID-Pad4)") (class "Default")
      (node (ref "USB_MICRO") (pin "4") (pinfunction "ID_4") (pintype "passive"))
    )
  )
)
